# obimon_0_2.net
KiCad netlist of a schematic drawn in EAGLE
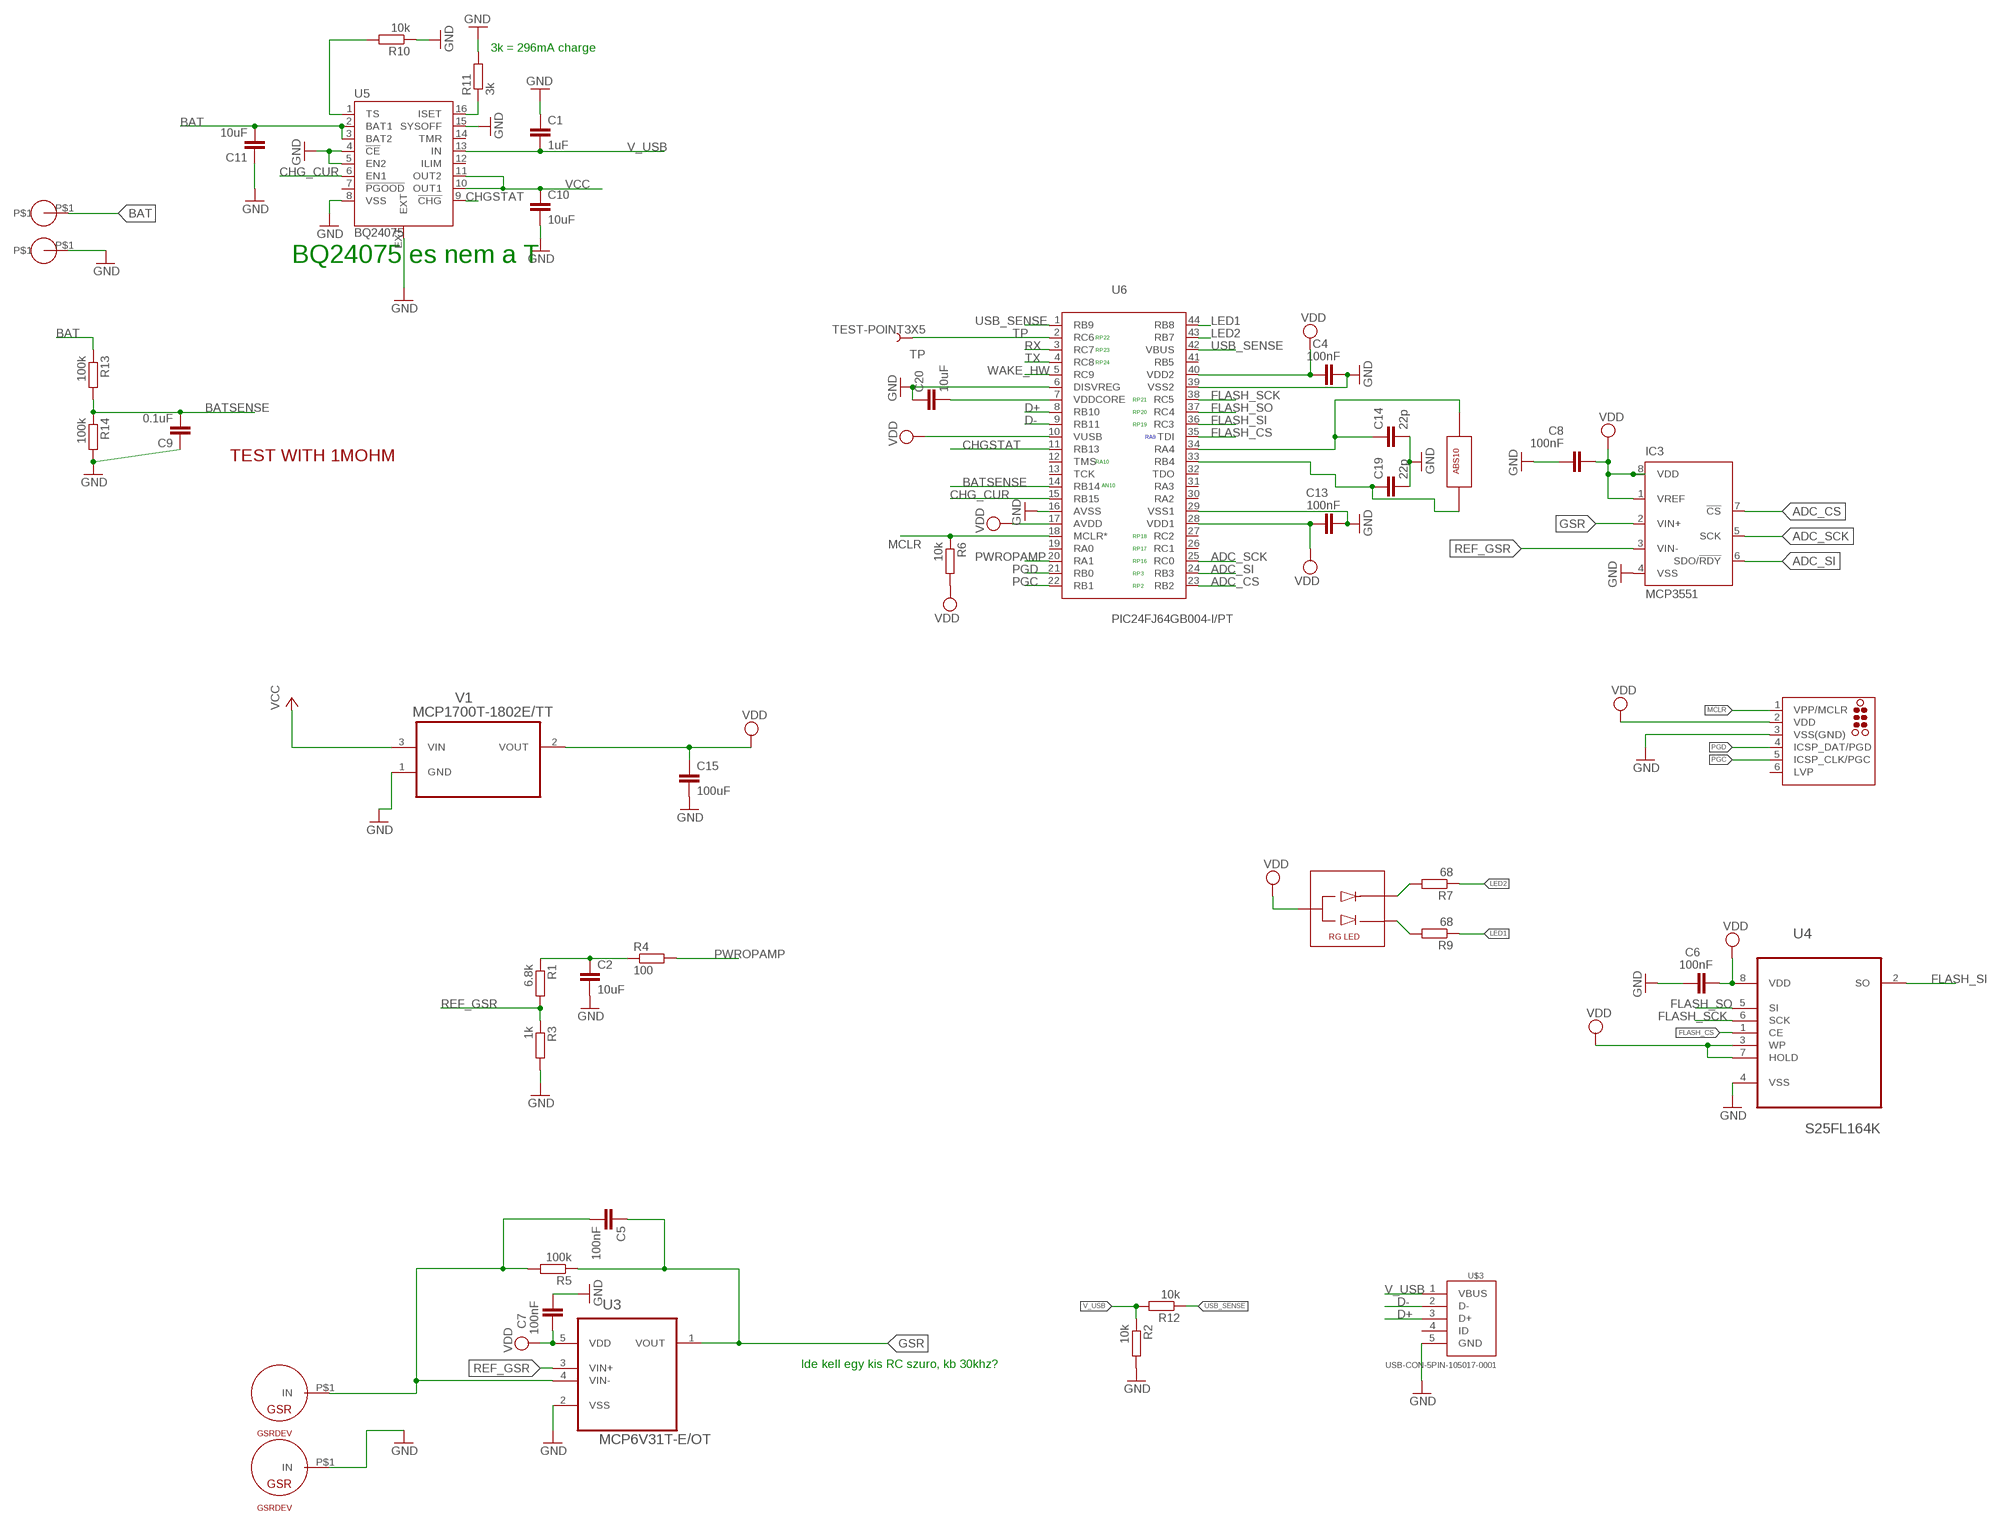
[diagram p0: schematic, sheet 1, part 1 of 2]
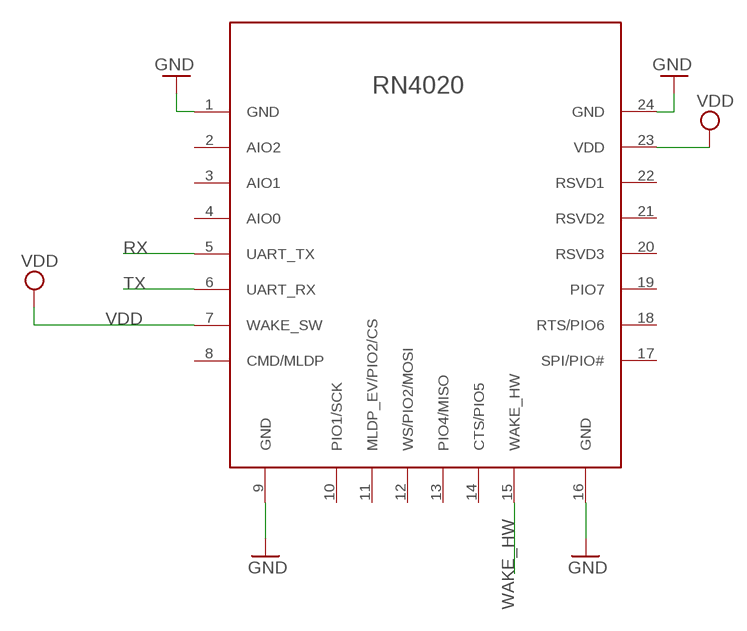
[diagram p1: schematic, sheet 1, part 2 of 2]

(export (version "E")
  (design (tool "Eeschema 10.0.6"))
  (components
    (comp (ref "C1")
      (value "1uF")
      (footprint "eagle-import:C0805")
      (libsource (lib "eagle-import") (part "C-EUC0805"))
    )
    (comp (ref "C2")
      (value "10uF")
      (footprint "eagle-import:C0805")
      (libsource (lib "eagle-import") (part "C-EUC0805"))
    )
    (comp (ref "C4")
      (value "100nF")
      (footprint "eagle-import:C0805")
      (libsource (lib "eagle-import") (part "C-EUC0805"))
    )
    (comp (ref "C5")
      (value "100nF")
      (footprint "eagle-import:C0805")
      (libsource (lib "eagle-import") (part "C-EUC0805"))
    )
    (comp (ref "C6")
      (value "100nF")
      (footprint "eagle-import:C0805")
      (libsource (lib "eagle-import") (part "C-EUC0805"))
    )
    (comp (ref "C7")
      (value "100nF")
      (footprint "eagle-import:C0805")
      (libsource (lib "eagle-import") (part "C-EUC0805"))
    )
    (comp (ref "C8")
      (value "100nF")
      (footprint "eagle-import:C0805")
      (libsource (lib "eagle-import") (part "C-EUC0805"))
    )
    (comp (ref "C9")
      (value "0.1uF")
      (footprint "eagle-import:C0805")
      (libsource (lib "eagle-import") (part "C-EUC0805"))
    )
    (comp (ref "C10")
      (value "10uF")
      (footprint "eagle-import:C0805")
      (libsource (lib "eagle-import") (part "C-EUC0805"))
    )
    (comp (ref "C11")
      (value "10uF")
      (footprint "eagle-import:C0805")
      (libsource (lib "eagle-import") (part "C-EUC0805"))
    )
    (comp (ref "C13")
      (value "100nF")
      (footprint "eagle-import:C0805")
      (libsource (lib "eagle-import") (part "C-EUC0805"))
    )
    (comp (ref "C14")
      (value "22p")
      (footprint "eagle-import:C0805")
      (libsource (lib "eagle-import") (part "C-EUC0805"))
    )
    (comp (ref "C15")
      (value "100uF")
      (footprint "eagle-import:1206")
      (libsource (lib "eagle-import") (part "CAP1206"))
    )
    (comp (ref "C19")
      (value "22p")
      (footprint "eagle-import:C0805")
      (libsource (lib "eagle-import") (part "C-EUC0805"))
    )
    (comp (ref "C20")
      (value "10uF")
      (footprint "eagle-import:C0805")
      (libsource (lib "eagle-import") (part "C-EUC0805"))
    )
    (comp (ref "IC3")
      (value "MCP3551")
      (footprint "eagle-import:SO-08")
      (fields (field (name "MPN") "MCP3551-E/SN"))
      (libsource (lib "eagle-import") (part "MCP355SN1"))
    )
    (comp (ref "J1")
      (value "TC2030-MCP-NL")
      (footprint "eagle-import:TC2030-MCP-NL")
      (libsource (lib "eagle-import") (part "TC2030-MCP-NL"))
    )
    (comp (ref "LED")
      (value "LED")
      (footprint "eagle-import:REDGREENLED")
      (libsource (lib "eagle-import") (part "REDGREENLED"))
    )
    (comp (ref "Q1")
      (value "ABS10")
      (footprint "eagle-import:ABS10")
      (libsource (lib "eagle-import") (part "ABS10"))
    )
    (comp (ref "R1")
      (value "6.8k")
      (footprint "eagle-import:R0805")
      (libsource (lib "eagle-import") (part "R-EU_R0805"))
    )
    (comp (ref "R2")
      (value "10k")
      (footprint "eagle-import:R0805")
      (libsource (lib "eagle-import") (part "R-EU_R0805"))
    )
    (comp (ref "R3")
      (value "1k")
      (footprint "eagle-import:R0805")
      (libsource (lib "eagle-import") (part "R-EU_R0805"))
    )
    (comp (ref "R4")
      (value "100")
      (footprint "eagle-import:R0805")
      (libsource (lib "eagle-import") (part "R-EU_R0805"))
    )
    (comp (ref "R5")
      (value "100k")
      (footprint "eagle-import:R0805")
      (libsource (lib "eagle-import") (part "R-EU_R0805"))
    )
    (comp (ref "R6")
      (value "10k")
      (footprint "eagle-import:M0805")
      (libsource (lib "eagle-import") (part "R-EU_M0805"))
    )
    (comp (ref "R7")
      (value "68")
      (footprint "eagle-import:R0805")
      (libsource (lib "eagle-import") (part "R-EU_R0805"))
    )
    (comp (ref "R9")
      (value "68")
      (footprint "eagle-import:R0805")
      (libsource (lib "eagle-import") (part "R-EU_R0805"))
    )
    (comp (ref "R10")
      (value "10k")
      (footprint "eagle-import:R0805")
      (libsource (lib "eagle-import") (part "R-EU_R0805"))
    )
    (comp (ref "R11")
      (value "3k")
      (footprint "eagle-import:R0805")
      (libsource (lib "eagle-import") (part "R-EU_R0805"))
    )
    (comp (ref "R12")
      (value "10k")
      (footprint "eagle-import:R0805")
      (libsource (lib "eagle-import") (part "R-EU_R0805"))
    )
    (comp (ref "R13")
      (value "100k")
      (footprint "eagle-import:R0805")
      (libsource (lib "eagle-import") (part "R-EU_R0805"))
    )
    (comp (ref "R14")
      (value "100k")
      (footprint "eagle-import:R0805")
      (libsource (lib "eagle-import") (part "R-EU_R0805"))
    )
    (comp (ref "TP")
      (value "TEST-POINT3X5")
      (footprint "eagle-import:PAD.03X.05")
      (libsource (lib "eagle-import") (part "TEST-POINT3X5"))
    )
    (comp (ref "U$1")
      (value "GSRDEV")
      (footprint "eagle-import:GSRPAD")
      (libsource (lib "eagle-import") (part "GSRDEV"))
    )
    (comp (ref "U$2")
      (value "GSRDEV")
      (footprint "eagle-import:GSRPAD")
      (libsource (lib "eagle-import") (part "GSRDEV"))
    )
    (comp (ref "U$3")
      (value "USB-CON-5PIN-105017-0001")
      (footprint "eagle-import:USB-MICRO-MOLEX-105017-0001")
      (libsource (lib "eagle-import") (part "USB-CON-5PIN-105017-0001"))
    )
    (comp (ref "U$6")
      (value "BATPAD")
      (footprint "eagle-import:BATPAD")
      (libsource (lib "eagle-import") (part "BATPAD"))
    )
    (comp (ref "U$7")
      (value "BATPAD")
      (footprint "eagle-import:BATPAD")
      (libsource (lib "eagle-import") (part "BATPAD"))
    )
    (comp (ref "U$8")
      (value "RN4020")
      (footprint "eagle-import:RN4020")
      (libsource (lib "eagle-import") (part "RN4020"))
    )
    (comp (ref "U3")
      (value "MCP6V31T-E/OT")
      (footprint "eagle-import:SOT95P290X145-5N")
      (libsource (lib "eagle-import") (part "MCP6V31T-E/OT"))
    )
    (comp (ref "U4")
      (value "S25FL164K")
      (footprint "eagle-import:SOIC127P790X216-8N")
      (libsource (lib "eagle-import") (part "S25FL164K"))
    )
    (comp (ref "U5")
      (value "BQ24075")
      (footprint "eagle-import:QFN16_3MM")
      (libsource (lib "eagle-import") (part "BQ24075"))
    )
    (comp (ref "U6")
      (value "PIC24FJ64GB004-I/PT")
      (footprint "eagle-import:QFP80P1200X1200X120-44N")
      (libsource (lib "eagle-import") (part "PIC24FJ64GB004-I/PT"))
    )
    (comp (ref "V1")
      (value "MCP1700T-1802E/TT")
      (footprint "eagle-import:SOT95P237X112-3N")
      (libsource (lib "eagle-import") (part "MCP1700T-1802E/TT"))
    )
  )
  (nets
    (net (code "1") (name "/BATSENSE") (class "Default")
      (node (ref "C9") (pin "2") (pinfunction "2_2") (pintype "passive"))
      (node (ref "R13") (pin "2") (pinfunction "2_2") (pintype "passive"))
      (node (ref "R14") (pin "1") (pinfunction "1_1") (pintype "passive"))
      (node (ref "U6") (pin "14") (pinfunction "RB14_14") (pintype "bidirectional"))
    )
    (net (code "2") (name "/CHGSTAT") (class "Default")
      (node (ref "U5") (pin "9") (pinfunction "~{CHG}_9") (pintype "bidirectional"))
      (node (ref "U6") (pin "11") (pinfunction "RB13_11") (pintype "bidirectional"))
    )
    (net (code "3") (name "/CHG_CUR") (class "Default")
      (node (ref "U5") (pin "6") (pinfunction "EN1_6") (pintype "bidirectional"))
      (node (ref "U6") (pin "15") (pinfunction "RB15_15") (pintype "bidirectional"))
    )
    (net (code "4") (name "/D+") (class "Default")
      (node (ref "U$3") (pin "3") (pinfunction "D+_3") (pintype "bidirectional"))
      (node (ref "U6") (pin "8") (pinfunction "RB10_8") (pintype "bidirectional"))
    )
    (net (code "5") (name "/D-") (class "Default")
      (node (ref "U$3") (pin "2") (pinfunction "D-_2") (pintype "bidirectional"))
      (node (ref "U6") (pin "9") (pinfunction "RB11_9") (pintype "bidirectional"))
    )
    (net (code "6") (name "/FLASH_SCK") (class "Default")
      (node (ref "U4") (pin "6") (pinfunction "SCK_6") (pintype "input"))
      (node (ref "U6") (pin "38") (pinfunction "RC5_38") (pintype "bidirectional"))
    )
    (net (code "7") (name "/FLASH_SI") (class "Default")
      (node (ref "U4") (pin "2") (pinfunction "SO_2") (pintype "output"))
      (node (ref "U6") (pin "36") (pinfunction "RC3_36") (pintype "bidirectional"))
    )
    (net (code "8") (name "/FLASH_SO") (class "Default")
      (node (ref "U4") (pin "5") (pinfunction "SI_5") (pintype "input"))
      (node (ref "U6") (pin "37") (pinfunction "RC4_37") (pintype "bidirectional"))
    )
    (net (code "9") (name "/PWROPAMP") (class "Default")
      (node (ref "R4") (pin "2") (pinfunction "2_2") (pintype "passive"))
      (node (ref "U6") (pin "20") (pinfunction "RA1_20") (pintype "bidirectional"))
    )
    (net (code "10") (name "/RX") (class "Default")
      (node (ref "U$8") (pin "5") (pinfunction "UART_TX_5") (pintype "bidirectional"))
      (node (ref "U6") (pin "3") (pinfunction "RC7_3") (pintype "bidirectional"))
    )
    (net (code "11") (name "/TP") (class "Default")
      (node (ref "TP") (pin "P$1") (pinfunction "1_P$1") (pintype "bidirectional"))
      (node (ref "U6") (pin "2") (pinfunction "RC6_2") (pintype "bidirectional"))
    )
    (net (code "12") (name "/TX") (class "Default")
      (node (ref "U$8") (pin "6") (pinfunction "UART_RX_6") (pintype "bidirectional"))
      (node (ref "U6") (pin "4") (pinfunction "RC8_4") (pintype "bidirectional"))
    )
    (net (code "13") (name "/WAKE_HW") (class "Default")
      (node (ref "U$8") (pin "15") (pinfunction "WAKE_HW_15") (pintype "bidirectional"))
      (node (ref "U6") (pin "5") (pinfunction "RC9_5") (pintype "bidirectional"))
    )
    (net (code "14") (name "ADC_CS") (class "Default")
      (node (ref "IC3") (pin "7") (pinfunction "~{CS}_7") (pintype "input"))
      (node (ref "U6") (pin "23") (pinfunction "RB2_23") (pintype "bidirectional"))
    )
    (net (code "15") (name "ADC_SCK") (class "Default")
      (node (ref "IC3") (pin "5") (pinfunction "SCK_5") (pintype "input"))
      (node (ref "U6") (pin "25") (pinfunction "RC0_25") (pintype "bidirectional"))
    )
    (net (code "16") (name "ADC_SI") (class "Default")
      (node (ref "IC3") (pin "6") (pinfunction "SDO/~{RDY}_6") (pintype "output"))
      (node (ref "U6") (pin "24") (pinfunction "RB3_24") (pintype "bidirectional"))
    )
    (net (code "17") (name "BAT") (class "Default")
      (node (ref "C11") (pin "2") (pinfunction "2_2") (pintype "passive"))
      (node (ref "R13") (pin "1") (pinfunction "1_1") (pintype "passive"))
      (node (ref "U$6") (pin "P$1") (pinfunction "P$1_P$1") (pintype "bidirectional"))
      (node (ref "U5") (pin "2") (pinfunction "BAT1_2") (pintype "bidirectional"))
      (node (ref "U5") (pin "3") (pinfunction "BAT2_3") (pintype "bidirectional"))
    )
    (net (code "18") (name "FLASH_CS") (class "Default")
      (node (ref "U4") (pin "1") (pinfunction "CE_1") (pintype "input"))
      (node (ref "U6") (pin "35") (pinfunction "TDI_35") (pintype "input"))
    )
    (net (code "19") (name "GND") (class "Default")
      (node (ref "C1") (pin "1") (pinfunction "1_1") (pintype "passive"))
      (node (ref "C10") (pin "2") (pinfunction "2_2") (pintype "passive"))
      (node (ref "C11") (pin "1") (pinfunction "1_1") (pintype "passive"))
      (node (ref "C13") (pin "2") (pinfunction "2_2") (pintype "passive"))
      (node (ref "C14") (pin "2") (pinfunction "2_2") (pintype "passive"))
      (node (ref "C15") (pin "2") (pinfunction "2_2") (pintype "passive"))
      (node (ref "C19") (pin "2") (pinfunction "2_2") (pintype "passive"))
      (node (ref "C2") (pin "2") (pinfunction "2_2") (pintype "passive"))
      (node (ref "C20") (pin "1") (pinfunction "1_1") (pintype "passive"))
      (node (ref "C4") (pin "2") (pinfunction "2_2") (pintype "passive"))
      (node (ref "C6") (pin "1") (pinfunction "1_1") (pintype "passive"))
      (node (ref "C7") (pin "2") (pinfunction "2_2") (pintype "passive"))
      (node (ref "C8") (pin "1") (pinfunction "1_1") (pintype "passive"))
      (node (ref "C9") (pin "1") (pinfunction "1_1") (pintype "passive"))
      (node (ref "IC3") (pin "4") (pinfunction "VSS_4") (pintype "power_in"))
      (node (ref "J1") (pin "3") (pinfunction "VSS(GND)_3") (pintype "power_in"))
      (node (ref "R10") (pin "1") (pinfunction "1_1") (pintype "passive"))
      (node (ref "R11") (pin "2") (pinfunction "2_2") (pintype "passive"))
      (node (ref "R14") (pin "2") (pinfunction "2_2") (pintype "passive"))
      (node (ref "R2") (pin "2") (pinfunction "2_2") (pintype "passive"))
      (node (ref "R3") (pin "2") (pinfunction "2_2") (pintype "passive"))
      (node (ref "U$2") (pin "P$1") (pinfunction "IN_P$1") (pintype "input"))
      (node (ref "U$3") (pin "5") (pinfunction "GND_5") (pintype "power_in"))
      (node (ref "U$7") (pin "P$1") (pinfunction "P$1_P$1") (pintype "bidirectional"))
      (node (ref "U$8") (pin "1") (pinfunction "GND_1") (pintype "power_in"))
      (node (ref "U$8") (pin "16") (pinfunction "GND_16") (pintype "power_in"))
      (node (ref "U$8") (pin "24") (pinfunction "GND_24") (pintype "power_in"))
      (node (ref "U$8") (pin "9") (pinfunction "GND_9") (pintype "power_in"))
      (node (ref "U3") (pin "2") (pinfunction "VSS_2") (pintype "power_in"))
      (node (ref "U4") (pin "4") (pinfunction "VSS_4") (pintype "passive"))
      (node (ref "U5") (pin "15") (pinfunction "SYSOFF_15") (pintype "bidirectional"))
      (node (ref "U5") (pin "4") (pinfunction "~{CE}_4") (pintype "bidirectional"))
      (node (ref "U5") (pin "5") (pinfunction "EN2_5") (pintype "bidirectional"))
      (node (ref "U5") (pin "8") (pinfunction "VSS_8") (pintype "bidirectional"))
      (node (ref "U5") (pin "EXT") (pinfunction "EXT_EXT") (pintype "bidirectional"))
      (node (ref "U6") (pin "16") (pinfunction "AVSS_16") (pintype "power_in"))
      (node (ref "U6") (pin "29") (pinfunction "VSS1_29") (pintype "power_in"))
      (node (ref "U6") (pin "39") (pinfunction "VSS2_39") (pintype "power_in"))
      (node (ref "U6") (pin "6") (pinfunction "DISVREG_6") (pintype "passive"))
      (node (ref "V1") (pin "1") (pinfunction "GND_1") (pintype "passive"))
    )
    (net (code "20") (name "GSR") (class "Default")
      (node (ref "C5") (pin "1") (pinfunction "1_1") (pintype "passive"))
      (node (ref "IC3") (pin "2") (pinfunction "VIN+_2") (pintype "input"))
      (node (ref "R5") (pin "1") (pinfunction "1_1") (pintype "passive"))
      (node (ref "U3") (pin "1") (pinfunction "VOUT_1") (pintype "output"))
    )
    (net (code "21") (name "LED1") (class "Default")
      (node (ref "R9") (pin "1") (pinfunction "1_1") (pintype "passive"))
      (node (ref "U6") (pin "44") (pinfunction "RB8_44") (pintype "bidirectional"))
    )
    (net (code "22") (name "LED2") (class "Default")
      (node (ref "R7") (pin "1") (pinfunction "1_1") (pintype "passive"))
      (node (ref "U6") (pin "43") (pinfunction "RB7_43") (pintype "bidirectional"))
    )
    (net (code "23") (name "MCLR") (class "Default")
      (node (ref "J1") (pin "1") (pinfunction "VPP/MCLR_1") (pintype "passive"))
      (node (ref "R6") (pin "1") (pinfunction "1_1") (pintype "passive"))
      (node (ref "U6") (pin "18") (pinfunction "MCLR*_18") (pintype "bidirectional"))
    )
    (net (code "24") (name "Net-(C2-Pad1)") (class "Default")
      (node (ref "C2") (pin "1") (pinfunction "1_1") (pintype "passive"))
      (node (ref "R1") (pin "1") (pinfunction "1_1") (pintype "passive"))
      (node (ref "R4") (pin "1") (pinfunction "1_1") (pintype "passive"))
    )
    (net (code "25") (name "Net-(LED-P$2)") (class "Default")
      (node (ref "LED") (pin "P$1") (pinfunction "P$2_P$1") (pintype "bidirectional"))
      (node (ref "R9") (pin "2") (pinfunction "2_2") (pintype "passive"))
    )
    (net (code "26") (name "Net-(LED-PadP$3)") (class "Default")
      (node (ref "LED") (pin "P$3") (pinfunction "P$3_P$3") (pintype "bidirectional"))
      (node (ref "R7") (pin "2") (pinfunction "2_2") (pintype "passive"))
    )
    (net (code "27") (name "Net-(U$1-IN)") (class "Default")
      (node (ref "C5") (pin "2") (pinfunction "2_2") (pintype "passive"))
      (node (ref "R5") (pin "2") (pinfunction "2_2") (pintype "passive"))
      (node (ref "U$1") (pin "P$1") (pinfunction "IN_P$1") (pintype "input"))
      (node (ref "U3") (pin "4") (pinfunction "VIN-_4") (pintype "input"))
    )
    (net (code "28") (name "Net-(U5-ISET)") (class "Default")
      (node (ref "R11") (pin "1") (pinfunction "1_1") (pintype "passive"))
      (node (ref "U5") (pin "16") (pinfunction "ISET_16") (pintype "bidirectional"))
    )
    (net (code "29") (name "Net-(U5-TS)") (class "Default")
      (node (ref "R10") (pin "2") (pinfunction "2_2") (pintype "passive"))
      (node (ref "U5") (pin "1") (pinfunction "TS_1") (pintype "bidirectional"))
    )
    (net (code "30") (name "Net-(U6-RA4)") (class "Default")
      (node (ref "C14") (pin "1") (pinfunction "1_1") (pintype "passive"))
      (node (ref "Q1") (pin "P$2") (pinfunction "P$2_P$2") (pintype "bidirectional"))
      (node (ref "U6") (pin "34") (pinfunction "RA4_34") (pintype "bidirectional"))
    )
    (net (code "31") (name "Net-(U6-RB4)") (class "Default")
      (node (ref "C19") (pin "1") (pinfunction "1_1") (pintype "passive"))
      (node (ref "Q1") (pin "P$1") (pinfunction "P$1_P$1") (pintype "bidirectional"))
      (node (ref "U6") (pin "33") (pinfunction "RB4_33") (pintype "bidirectional"))
    )
    (net (code "32") (name "Net-(U6-VDDCORE)") (class "Default")
      (node (ref "C20") (pin "2") (pinfunction "2_2") (pintype "passive"))
      (node (ref "U6") (pin "7") (pinfunction "VDDCORE_7") (pintype "power_in"))
    )
    (net (code "33") (name "PGC") (class "Default")
      (node (ref "J1") (pin "5") (pinfunction "ICSP_CLK/PGC_5") (pintype "output"))
      (node (ref "U6") (pin "22") (pinfunction "RB1_22") (pintype "bidirectional"))
    )
    (net (code "34") (name "PGD") (class "Default")
      (node (ref "J1") (pin "4") (pinfunction "ICSP_DAT/PGD_4") (pintype "bidirectional"))
      (node (ref "U6") (pin "21") (pinfunction "RB0_21") (pintype "bidirectional"))
    )
    (net (code "35") (name "REF_GSR") (class "Default")
      (node (ref "IC3") (pin "3") (pinfunction "VIN-_3") (pintype "input"))
      (node (ref "R1") (pin "2") (pinfunction "2_2") (pintype "passive"))
      (node (ref "R3") (pin "1") (pinfunction "1_1") (pintype "passive"))
      (node (ref "U3") (pin "3") (pinfunction "VIN+_3") (pintype "input"))
    )
    (net (code "36") (name "USB_SENSE") (class "Default")
      (node (ref "R12") (pin "1") (pinfunction "1_1") (pintype "passive"))
      (node (ref "U6") (pin "1") (pinfunction "RB9_1") (pintype "bidirectional"))
      (node (ref "U6") (pin "42") (pinfunction "VBUS_42") (pintype "passive"))
    )
    (net (code "37") (name "VCC") (class "Default")
      (node (ref "C10") (pin "1") (pinfunction "1_1") (pintype "passive"))
      (node (ref "U5") (pin "10") (pinfunction "OUT1_10") (pintype "bidirectional"))
      (node (ref "U5") (pin "11") (pinfunction "OUT2_11") (pintype "bidirectional"))
      (node (ref "V1") (pin "3") (pinfunction "VIN_3") (pintype "input"))
    )
    (net (code "38") (name "VDD") (class "Default")
      (node (ref "C13") (pin "1") (pinfunction "1_1") (pintype "passive"))
      (node (ref "C15") (pin "1") (pinfunction "1_1") (pintype "passive"))
      (node (ref "C4") (pin "1") (pinfunction "1_1") (pintype "passive"))
      (node (ref "C6") (pin "2") (pinfunction "2_2") (pintype "passive"))
      (node (ref "C7") (pin "1") (pinfunction "1_1") (pintype "passive"))
      (node (ref "C8") (pin "2") (pinfunction "2_2") (pintype "passive"))
      (node (ref "IC3") (pin "1") (pinfunction "VREF_1") (pintype "input"))
      (node (ref "IC3") (pin "8") (pinfunction "VDD_8") (pintype "power_in"))
      (node (ref "J1") (pin "2") (pinfunction "VDD_2") (pintype "power_in"))
      (node (ref "LED") (pin "P$2") (pinfunction "P$1_P$2") (pintype "bidirectional"))
      (node (ref "R6") (pin "2") (pinfunction "2_2") (pintype "passive"))
      (node (ref "U$8") (pin "23") (pinfunction "VDD_23") (pintype "power_in"))
      (node (ref "U$8") (pin "7") (pinfunction "WAKE_SW_7") (pintype "bidirectional"))
      (node (ref "U3") (pin "5") (pinfunction "VDD_5") (pintype "power_in"))
      (node (ref "U4") (pin "3") (pinfunction "WP_3") (pintype "input"))
      (node (ref "U4") (pin "7") (pinfunction "HOLD_7") (pintype "input"))
      (node (ref "U4") (pin "8") (pinfunction "VDD_8") (pintype "power_in"))
      (node (ref "U6") (pin "10") (pinfunction "VUSB_10") (pintype "passive"))
      (node (ref "U6") (pin "17") (pinfunction "AVDD_17") (pintype "power_in"))
      (node (ref "U6") (pin "28") (pinfunction "VDD1_28") (pintype "power_in"))
      (node (ref "U6") (pin "40") (pinfunction "VDD2_40") (pintype "power_in"))
      (node (ref "V1") (pin "2") (pinfunction "VOUT_2") (pintype "output"))
    )
    (net (code "39") (name "V_USB") (class "Default")
      (node (ref "C1") (pin "2") (pinfunction "2_2") (pintype "passive"))
      (node (ref "R12") (pin "2") (pinfunction "2_2") (pintype "passive"))
      (node (ref "R2") (pin "1") (pinfunction "1_1") (pintype "passive"))
      (node (ref "U$3") (pin "1") (pinfunction "VBUS_1") (pintype "power_in"))
      (node (ref "U5") (pin "13") (pinfunction "IN_13") (pintype "bidirectional"))
    )
    (net (code "40") (name "unconnected-(J1-LVP-Pad6)") (class "Default")
      (node (ref "J1") (pin "6") (pinfunction "LVP_6") (pintype "bidirectional"))
    )
    (net (code "41") (name "unconnected-(U$3-ID-Pad4)") (class "Default")
      (node (ref "U$3") (pin "4") (pinfunction "ID_4") (pintype "bidirectional"))
    )
    (net (code "42") (name "unconnected-(U$8-AIO0-Pad4)") (class "Default")
      (node (ref "U$8") (pin "4") (pinfunction "AIO0_4") (pintype "bidirectional"))
    )
    (net (code "43") (name "unconnected-(U$8-AIO1-Pad3)") (class "Default")
      (node (ref "U$8") (pin "3") (pinfunction "AIO1_3") (pintype "bidirectional"))
    )
    (net (code "44") (name "unconnected-(U$8-AIO2-Pad2)") (class "Default")
      (node (ref "U$8") (pin "2") (pinfunction "AIO2_2") (pintype "bidirectional"))
    )
    (net (code "45") (name "unconnected-(U$8-CMD{slash}MLDP-Pad8)") (class "Default")
      (node (ref "U$8") (pin "8") (pinfunction "CMD/MLDP_8") (pintype "bidirectional"))
    )
    (net (code "46") (name "unconnected-(U$8-CTS{slash}PIO5-Pad14)") (class "Default")
      (node (ref "U$8") (pin "14") (pinfunction "CTS/PIO5_14") (pintype "bidirectional"))
    )
    (net (code "47") (name "unconnected-(U$8-MLDP_EV{slash}PIO2{slash}CS-Pad11)") (class "Default")
      (node (ref "U$8") (pin "11") (pinfunction "MLDP_EV/PIO2/CS_11") (pintype "bidirectional"))
    )
    (net (code "48") (name "unconnected-(U$8-PIO1{slash}SCK-Pad10)") (class "Default")
      (node (ref "U$8") (pin "10") (pinfunction "PIO1/SCK_10") (pintype "bidirectional"))
    )
    (net (code "49") (name "unconnected-(U$8-PIO4{slash}MISO-Pad13)") (class "Default")
      (node (ref "U$8") (pin "13") (pinfunction "PIO4/MISO_13") (pintype "bidirectional"))
    )
    (net (code "50") (name "unconnected-(U$8-PIO7-Pad19)") (class "Default")
      (node (ref "U$8") (pin "19") (pinfunction "PIO7_19") (pintype "bidirectional"))
    )
    (net (code "51") (name "unconnected-(U$8-RSVD1-Pad22)") (class "Default")
      (node (ref "U$8") (pin "22") (pinfunction "RSVD1_22") (pintype "bidirectional"))
    )
    (net (code "52") (name "unconnected-(U$8-RSVD2-Pad21)") (class "Default")
      (node (ref "U$8") (pin "21") (pinfunction "RSVD2_21") (pintype "bidirectional"))
    )
    (net (code "53") (name "unconnected-(U$8-RSVD3-Pad20)") (class "Default")
      (node (ref "U$8") (pin "20") (pinfunction "RSVD3_20") (pintype "bidirectional"))
    )
    (net (code "54") (name "unconnected-(U$8-RTS{slash}PIO6-Pad18)") (class "Default")
      (node (ref "U$8") (pin "18") (pinfunction "RTS/PIO6_18") (pintype "bidirectional"))
    )
    (net (code "55") (name "unconnected-(U$8-SPI{slash}PIO#-Pad17)") (class "Default")
      (node (ref "U$8") (pin "17") (pinfunction "SPI/PIO#_17") (pintype "bidirectional"))
    )
    (net (code "56") (name "unconnected-(U$8-WS{slash}PIO2{slash}MOSI-Pad12)") (class "Default")
      (node (ref "U$8") (pin "12") (pinfunction "WS/PIO2/MOSI_12") (pintype "bidirectional"))
    )
    (net (code "57") (name "unconnected-(U5-ILIM-Pad12)") (class "Default")
      (node (ref "U5") (pin "12") (pinfunction "ILIM_12") (pintype "bidirectional"))
    )
    (net (code "58") (name "unconnected-(U5-TMR-Pad14)") (class "Default")
      (node (ref "U5") (pin "14") (pinfunction "TMR_14") (pintype "bidirectional"))
    )
    (net (code "59") (name "unconnected-(U5-~{PGOOD}-Pad7)") (class "Default")
      (node (ref "U5") (pin "7") (pinfunction "~{PGOOD}_7") (pintype "bidirectional"))
    )
    (net (code "60") (name "unconnected-(U6-RA0-Pad19)") (class "Default")
      (node (ref "U6") (pin "19") (pinfunction "RA0_19") (pintype "bidirectional"))
    )
    (net (code "61") (name "unconnected-(U6-RA2-Pad30)") (class "Default")
      (node (ref "U6") (pin "30") (pinfunction "RA2_30") (pintype "bidirectional"))
    )
    (net (code "62") (name "unconnected-(U6-RA3-Pad31)") (class "Default")
      (node (ref "U6") (pin "31") (pinfunction "RA3_31") (pintype "bidirectional"))
    )
    (net (code "63") (name "unconnected-(U6-RB5-Pad41)") (class "Default")
      (node (ref "U6") (pin "41") (pinfunction "RB5_41") (pintype "bidirectional"))
    )
    (net (code "64") (name "unconnected-(U6-RC1-Pad26)") (class "Default")
      (node (ref "U6") (pin "26") (pinfunction "RC1_26") (pintype "bidirectional"))
    )
    (net (code "65") (name "unconnected-(U6-RC2-Pad27)") (class "Default")
      (node (ref "U6") (pin "27") (pinfunction "RC2_27") (pintype "bidirectional"))
    )
    (net (code "66") (name "unconnected-(U6-TCK-Pad13)") (class "Default")
      (node (ref "U6") (pin "13") (pinfunction "TCK_13") (pintype "input"))
    )
    (net (code "67") (name "unconnected-(U6-TDO-Pad32)") (class "Default")
      (node (ref "U6") (pin "32") (pinfunction "TDO_32") (pintype "output"))
    )
    (net (code "68") (name "unconnected-(U6-TMS-Pad12)") (class "Default")
      (node (ref "U6") (pin "12") (pinfunction "TMS_12") (pintype "input"))
    )
  )
)
